# VolumePot.net
KiCad netlist of a schematic drawn in EAGLE
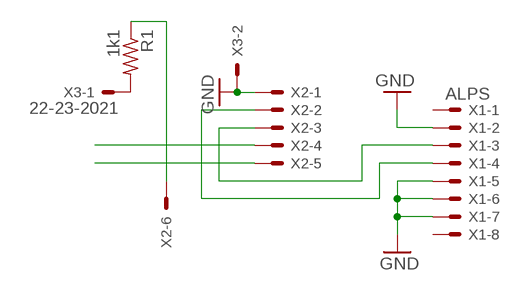
[diagram p0: schematic, sheet 1]

(export (version "E")
  (design (tool "Eeschema 10.0.6"))
  (components
    (comp (ref "R1")
      (value "1k1")
      (footprint "eagle-import:0309_12")
      (libsource (lib "eagle-import") (part "R-US_0309/12"))
    )
    (comp (ref "X1")
      (value "ALPS")
      (footprint "eagle-import:22-23-2081")
      (fields (field (name "MF") "MOLEX") (field (name "MPN") "22-23-2081"))
      (libsource (lib "eagle-import") (part "22-23-2081"))
    )
    (comp (ref "X2")
      (value "22-23-2061")
      (footprint "eagle-import:22-23-2061")
      (fields (field (name "MF") "MOLEX"))
      (libsource (lib "eagle-import") (part "22-23-2061"))
    )
    (comp (ref "X3")
      (value "22-23-2021")
      (footprint "eagle-import:22-23-2021")
      (fields (field (name "MF") "MOLEX"))
      (libsource (lib "eagle-import") (part "22-23-2021"))
    )
  )
  (nets
    (net (code "1") (name "GND") (class "Default")
      (node (ref "X1") (pin "2") (pinfunction "S_2") (pintype "passive"))
      (node (ref "X1") (pin "5") (pinfunction "S_5") (pintype "passive"))
      (node (ref "X1") (pin "6") (pinfunction "S_6") (pintype "passive"))
      (node (ref "X1") (pin "7") (pinfunction "S_7") (pintype "passive"))
      (node (ref "X2") (pin "1") (pinfunction "S_1") (pintype "passive"))
      (node (ref "X3") (pin "2") (pinfunction "S_2") (pintype "passive"))
    )
    (net (code "2") (name "Net-(X1C-S)") (class "Default")
      (node (ref "X1") (pin "3") (pinfunction "S_3") (pintype "passive"))
      (node (ref "X2") (pin "3") (pinfunction "S_3") (pintype "passive"))
    )
    (net (code "3") (name "Net-(X1D-S)") (class "Default")
      (node (ref "X1") (pin "4") (pinfunction "S_4") (pintype "passive"))
      (node (ref "X2") (pin "2") (pinfunction "S_2") (pintype "passive"))
    )
    (net (code "4") (name "Net-(X2F-S)") (class "Default")
      (node (ref "R1") (pin "1") (pinfunction "1_1") (pintype "passive"))
      (node (ref "X2") (pin "6") (pinfunction "S_6") (pintype "passive"))
    )
    (net (code "5") (name "Net-(X3A-S)") (class "Default")
      (node (ref "R1") (pin "2") (pinfunction "2_2") (pintype "passive"))
      (node (ref "X3") (pin "1") (pinfunction "S_1") (pintype "passive"))
    )
    (net (code "6") (name "unconnected-(X1A-S-Pad1)") (class "Default")
      (node (ref "X1") (pin "1") (pinfunction "S_1") (pintype "passive"))
    )
    (net (code "7") (name "unconnected-(X1H-S-Pad8)") (class "Default")
      (node (ref "X1") (pin "8") (pinfunction "S_8") (pintype "passive"))
    )
    (net (code "8") (name "unconnected-(X2D-S-Pad4)") (class "Default")
      (node (ref "X2") (pin "4") (pinfunction "S_4") (pintype "passive"))
    )
    (net (code "9") (name "unconnected-(X2E-S-Pad5)") (class "Default")
      (node (ref "X2") (pin "5") (pinfunction "S_5") (pintype "passive"))
    )
  )
)
